# openSX70_ALADDIN_V37_20180120.net
KiCad netlist of a schematic drawn in EAGLE
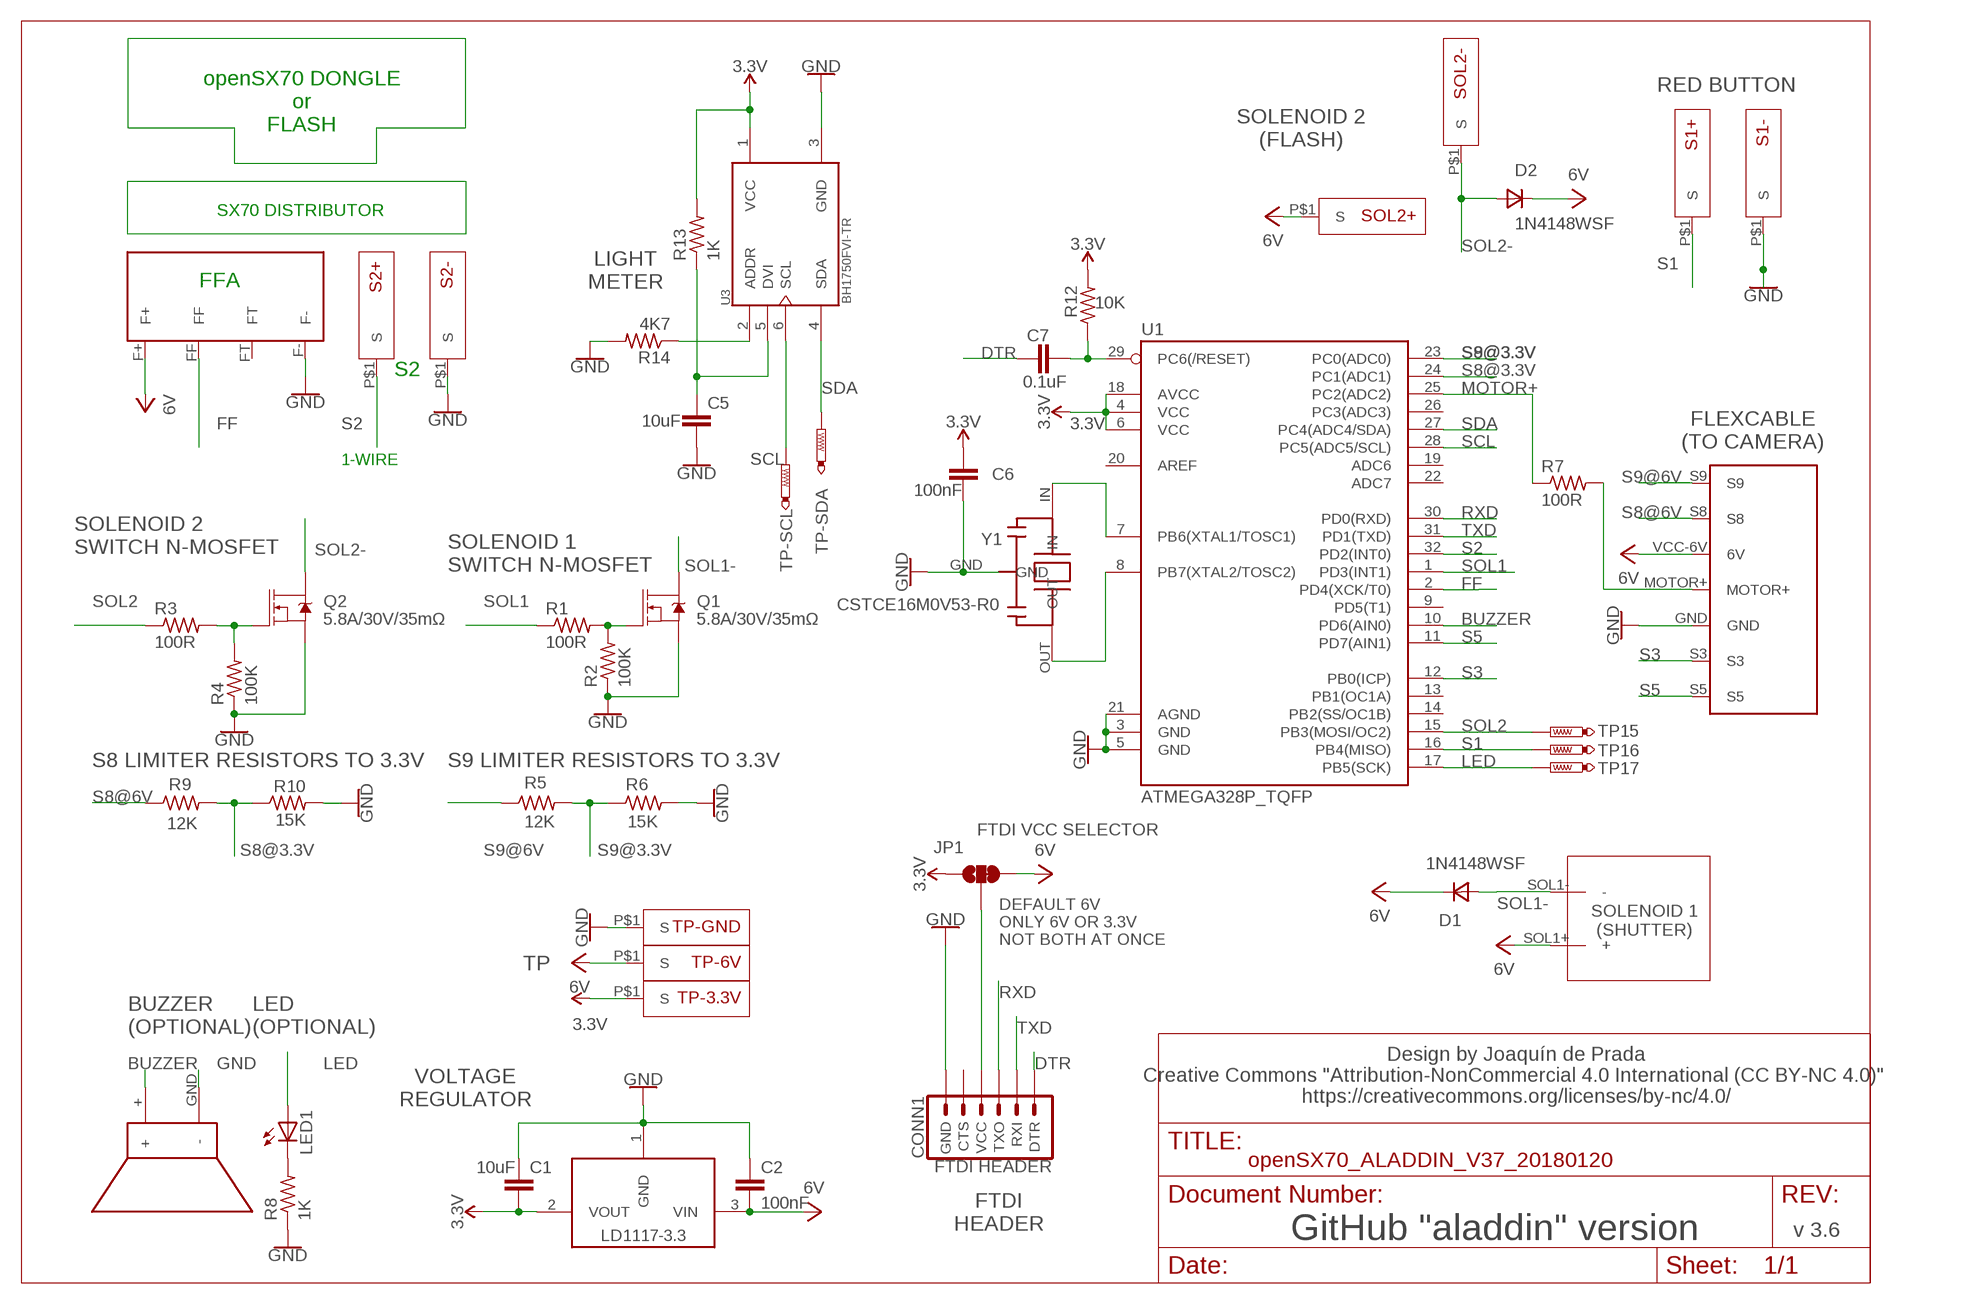
[diagram p0: schematic, sheet 1]

(export (version "E")
  (design (tool "Eeschema 10.0.6"))
  (components
    (comp (ref "BUZZ1")
      (value "CSET8-5G")
      (footprint "eagle-import:CSET8-5G_PACKAGE")
      (libsource (lib "eagle-import") (part "CSET8-5G"))
    )
    (comp (ref "C1")
      (value "10uF")
      (footprint "eagle-import:0603")
      (libsource (lib "eagle-import") (part "10UF-0603-6.3V-20%"))
    )
    (comp (ref "C2")
      (value "100nF")
      (footprint "eagle-import:C0603K")
      (libsource (lib "eagle-import") (part "C-EUC0603K"))
    )
    (comp (ref "C5")
      (value "10uF")
      (footprint "eagle-import:0603")
      (libsource (lib "eagle-import") (part "10UF-0603-6.3V-20%"))
    )
    (comp (ref "C6")
      (value "100nF")
      (footprint "eagle-import:C0603")
      (libsource (lib "eagle-import") (part "C-EUC0603"))
    )
    (comp (ref "C7")
      (value "0.1uF")
      (footprint "eagle-import:0603")
      (libsource (lib "eagle-import") (part "0.1UF-0603-25V-(+80/-20%)"))
    )
    (comp (ref "CONN1")
      (value "FTDI HEADER")
      (footprint "eagle-import:1X06")
      (libsource (lib "eagle-import") (part "6_PIN_SERIAL_TARGET"))
    )
    (comp (ref "D1")
      (value "1N4148WSF")
      (footprint "eagle-import:SOD323")
      (fields (field (name "MPN") "CDSOD323-T05C"))
      (libsource (lib "eagle-import") (part "DSOD323"))
    )
    (comp (ref "D2")
      (value "1N4148WSF")
      (footprint "eagle-import:SOD323")
      (fields (field (name "MPN") "CDSOD323-T05C"))
      (libsource (lib "eagle-import") (part "DSOD323"))
    )
    (comp (ref "JP1")
      (value "FTDI VCC SELECTOR")
      (footprint "eagle-import:SMT-JUMPER_3_1-NC_TRACE_SILK")
      (libsource (lib "eagle-import") (part "JUMPER-SMT_3_1-NC_TRACE_SILK"))
    )
    (comp (ref "LD11173.3V")
      (value "LD1117 3.3V")
      (footprint "eagle-import:SOT223")
      (fields (field (name "MF") "Advanced Monolithic Systems") (field (name "MP") "AMS1117-5.0"))
      (libsource (lib "eagle-import") (part "LD1117-3.3"))
    )
    (comp (ref "LED1")
      (value "LEDCHIPLED_0805")
      (footprint "eagle-import:CHIPLED_0805")
      (libsource (lib "eagle-import") (part "LEDCHIPLED_0805"))
    )
    (comp (ref "Q1")
      (value "5.8A/30V/35mΩ")
      (footprint "eagle-import:SOT23-3")
      (libsource (lib "eagle-import") (part "MOSFET-NCH-AO3404A"))
    )
    (comp (ref "Q2")
      (value "5.8A/30V/35mΩ")
      (footprint "eagle-import:SOT23-3")
      (libsource (lib "eagle-import") (part "MOSFET-NCH-AO3404A"))
    )
    (comp (ref "R1")
      (value "100R")
      (footprint "eagle-import:R0603")
      (libsource (lib "eagle-import") (part "R-US_R0603"))
    )
    (comp (ref "R2")
      (value "100K")
      (footprint "eagle-import:R0603")
      (libsource (lib "eagle-import") (part "R-US_R0603"))
    )
    (comp (ref "R3")
      (value "100R")
      (footprint "eagle-import:R0603")
      (libsource (lib "eagle-import") (part "R-US_R0603"))
    )
    (comp (ref "R4")
      (value "100K")
      (footprint "eagle-import:R0603")
      (libsource (lib "eagle-import") (part "R-US_R0603"))
    )
    (comp (ref "R5")
      (value "12K")
      (footprint "eagle-import:R0603")
      (libsource (lib "eagle-import") (part "R-US_R0603"))
    )
    (comp (ref "R6")
      (value "15K")
      (footprint "eagle-import:R0603")
      (libsource (lib "eagle-import") (part "R-US_R0603"))
    )
    (comp (ref "R7")
      (value "100R")
      (footprint "eagle-import:R0603")
      (libsource (lib "eagle-import") (part "R-US_R0603"))
    )
    (comp (ref "R8")
      (value "1K")
      (footprint "eagle-import:R0603")
      (libsource (lib "eagle-import") (part "R-US_R0603"))
    )
    (comp (ref "R9")
      (value "12K")
      (footprint "eagle-import:R0603")
      (libsource (lib "eagle-import") (part "R-US_R0603"))
    )
    (comp (ref "R10")
      (value "15K")
      (footprint "eagle-import:R0603")
      (libsource (lib "eagle-import") (part "R-US_R0603"))
    )
    (comp (ref "R12")
      (value "10K")
      (footprint "eagle-import:R0603")
      (libsource (lib "eagle-import") (part "R-US_R0603"))
    )
    (comp (ref "R13")
      (value "1K")
      (footprint "eagle-import:R0603")
      (libsource (lib "eagle-import") (part "R-US_R0603"))
    )
    (comp (ref "R14")
      (value "4K7")
      (footprint "eagle-import:R0603")
      (libsource (lib "eagle-import") (part "R-US_R0603"))
    )
    (comp (ref "S1+")
      (value "SX70-S-PAD-NEW")
      (footprint "eagle-import:SX70-S-PAD2")
      (libsource (lib "eagle-import") (part "SX70-S-PAD-NEW"))
    )
    (comp (ref "S1-")
      (value "SX70-S-PAD-NEW")
      (footprint "eagle-import:SX70-S-PAD2")
      (libsource (lib "eagle-import") (part "SX70-S-PAD-NEW"))
    )
    (comp (ref "S2+")
      (value "SX70-S-PAD-NEW")
      (footprint "eagle-import:SX70-S-PAD2")
      (libsource (lib "eagle-import") (part "SX70-S-PAD-NEW"))
    )
    (comp (ref "S2-")
      (value "SX70-S-PAD-NEW")
      (footprint "eagle-import:SX70-S-PAD2")
      (libsource (lib "eagle-import") (part "SX70-S-PAD-NEW"))
    )
    (comp (ref "SOL1")
      (value "SX70-SOLENOID1-2PADS")
      (footprint "eagle-import:SX70-SOLENOID1-2")
      (libsource (lib "eagle-import") (part "SX70-SOLENOID1-2PADS"))
    )
    (comp (ref "SOL2+")
      (value "SX70-S-PAD-NEW")
      (footprint "eagle-import:SX70-S-PAD2")
      (libsource (lib "eagle-import") (part "SX70-S-PAD-NEW"))
    )
    (comp (ref "SOL2-")
      (value "SX70-S-PAD-NEW")
      (footprint "eagle-import:SX70-S-PAD2")
      (libsource (lib "eagle-import") (part "SX70-S-PAD-NEW"))
    )
    (comp (ref "TP-3.3V")
      (value "SX70-S-PAD-NEW")
      (footprint "eagle-import:SX70-S-PAD2")
      (libsource (lib "eagle-import") (part "SX70-S-PAD-NEW"))
    )
    (comp (ref "TP-6V")
      (value "SX70-S-PAD-NEW")
      (footprint "eagle-import:SX70-S-PAD2")
      (libsource (lib "eagle-import") (part "SX70-S-PAD-NEW"))
    )
    (comp (ref "TP-GND")
      (value "SX70-S-PAD-NEW")
      (footprint "eagle-import:SX70-S-PAD2")
      (libsource (lib "eagle-import") (part "SX70-S-PAD-NEW"))
    )
    (comp (ref "TP-SCL")
      (value "PTR1TP08R")
      (footprint "eagle-import:TP08R")
      (libsource (lib "eagle-import") (part "PTR1TP08R"))
    )
    (comp (ref "TP-SDA")
      (value "PTR1TP08R")
      (footprint "eagle-import:TP08R")
      (libsource (lib "eagle-import") (part "PTR1TP08R"))
    )
    (comp (ref "TP15")
      (value "PTR1TP08R")
      (footprint "eagle-import:TP08R")
      (libsource (lib "eagle-import") (part "PTR1TP08R"))
    )
    (comp (ref "TP16")
      (value "PTR1TP08R")
      (footprint "eagle-import:TP08R")
      (libsource (lib "eagle-import") (part "PTR1TP08R"))
    )
    (comp (ref "TP17")
      (value "PTR1TP08R")
      (footprint "eagle-import:TP08R")
      (libsource (lib "eagle-import") (part "PTR1TP08R"))
    )
    (comp (ref "U$1")
      (value "SX70-7-PAD")
      (footprint "eagle-import:SX70-7-PAD")
      (libsource (lib "eagle-import") (part "SX70-7-PAD"))
    )
    (comp (ref "U$2")
      (value "FFA")
      (footprint "eagle-import:FFA-PAD-PACKAGE")
      (libsource (lib "eagle-import") (part "SX70-FFA-PAD"))
    )
    (comp (ref "U1")
      (value "ATMEGA328P_TQFP")
      (footprint "eagle-import:TQFP32-08")
      (libsource (lib "eagle-import") (part "ATMEGA328P_TQFP"))
    )
    (comp (ref "U3")
      (value "BH1750FVI-TR")
      (footprint "eagle-import:SOTFL50P300X75-6N")
      (fields (field (name "MF") "Rohm"))
      (libsource (lib "eagle-import") (part "BH1750FVI-TR"))
    )
    (comp (ref "Y1")
      (value "CSTCE16M0V53-R0")
      (footprint "eagle-import:CFP95P160X100-3N")
      (fields (field (name "MF") "Murata"))
      (libsource (lib "eagle-import") (part "CSTCE16M0V53-R0"))
    )
  )
  (nets
    (net (code "1") (name "/BUZZER") (class "Default")
      (node (ref "BUZZ1") (pin "+") (pinfunction "+_+") (pintype "bidirectional"))
      (node (ref "U1") (pin "10") (pinfunction "PD6(AIN0)_10") (pintype "bidirectional"))
    )
    (net (code "2") (name "/DTR") (class "Default")
      (node (ref "C7") (pin "1") (pinfunction "1_1") (pintype "passive"))
      (node (ref "CONN1") (pin "1") (pinfunction "DTR_1") (pintype "passive"))
    )
    (net (code "3") (name "/FF") (class "Default")
      (node (ref "U$2") (pin "FF") (pinfunction "FF_FF") (pintype "bidirectional"))
      (node (ref "U1") (pin "2") (pinfunction "PD4(XCK/T0)_2") (pintype "bidirectional"))
    )
    (net (code "4") (name "/LED") (class "Default")
      (node (ref "LED1") (pin "A") (pinfunction "A_A") (pintype "passive"))
      (node (ref "TP17") (pin "TP") (pinfunction "TP_TP") (pintype "input"))
      (node (ref "U1") (pin "17") (pinfunction "PB5(SCK)_17") (pintype "bidirectional"))
    )
    (net (code "5") (name "/MOTOR+") (class "Default")
      (node (ref "R7") (pin "1") (pinfunction "1_1") (pintype "passive"))
      (node (ref "U1") (pin "25") (pinfunction "PC2(ADC2)_25") (pintype "bidirectional"))
    )
    (net (code "6") (name "/RXD") (class "Default")
      (node (ref "CONN1") (pin "3") (pinfunction "TXO_3") (pintype "passive"))
      (node (ref "U1") (pin "30") (pinfunction "PD0(RXD)_30") (pintype "bidirectional"))
    )
    (net (code "7") (name "/S1") (class "Default")
      (node (ref "S1+") (pin "P$1") (pinfunction "S_P$1") (pintype "bidirectional"))
      (node (ref "TP16") (pin "TP") (pinfunction "TP_TP") (pintype "input"))
      (node (ref "U1") (pin "16") (pinfunction "PB4(MISO)_16") (pintype "bidirectional"))
    )
    (net (code "8") (name "/S2") (class "Default")
      (node (ref "S2+") (pin "P$1") (pinfunction "S_P$1") (pintype "bidirectional"))
      (node (ref "U1") (pin "32") (pinfunction "PD2(INT0)_32") (pintype "bidirectional"))
    )
    (net (code "9") (name "/S3") (class "Default")
      (node (ref "U$1") (pin "S3") (pinfunction "S3_S3") (pintype "bidirectional"))
      (node (ref "U1") (pin "12") (pinfunction "PB0(ICP)_12") (pintype "bidirectional"))
    )
    (net (code "10") (name "/S5") (class "Default")
      (node (ref "U$1") (pin "S5") (pinfunction "S5_S5") (pintype "bidirectional"))
      (node (ref "U1") (pin "11") (pinfunction "PD7(AIN1)_11") (pintype "bidirectional"))
    )
    (net (code "11") (name "/S8@3.3V") (class "Default")
      (node (ref "R10") (pin "1") (pinfunction "1_1") (pintype "passive"))
      (node (ref "R9") (pin "2") (pinfunction "2_2") (pintype "passive"))
      (node (ref "U1") (pin "24") (pinfunction "PC1(ADC1)_24") (pintype "bidirectional"))
    )
    (net (code "12") (name "/S8@6V") (class "Default")
      (node (ref "R9") (pin "1") (pinfunction "1_1") (pintype "passive"))
      (node (ref "U$1") (pin "S8") (pinfunction "S8_S8") (pintype "bidirectional"))
    )
    (net (code "13") (name "/S9@3.3V") (class "Default")
      (node (ref "R5") (pin "2") (pinfunction "2_2") (pintype "passive"))
      (node (ref "R6") (pin "1") (pinfunction "1_1") (pintype "passive"))
      (node (ref "U1") (pin "23") (pinfunction "PC0(ADC0)_23") (pintype "bidirectional"))
    )
    (net (code "14") (name "/S9@6V") (class "Default")
      (node (ref "R5") (pin "1") (pinfunction "1_1") (pintype "passive"))
      (node (ref "U$1") (pin "S9") (pinfunction "S9_S9") (pintype "bidirectional"))
    )
    (net (code "15") (name "/SCL") (class "Default")
      (node (ref "TP-SCL") (pin "TP") (pinfunction "TP_TP") (pintype "input"))
      (node (ref "U1") (pin "28") (pinfunction "PC5(ADC5/SCL)_28") (pintype "bidirectional"))
      (node (ref "U3") (pin "6") (pinfunction "SCL_6") (pintype "input"))
    )
    (net (code "16") (name "/SDA") (class "Default")
      (node (ref "TP-SDA") (pin "TP") (pinfunction "TP_TP") (pintype "input"))
      (node (ref "U1") (pin "27") (pinfunction "PC4(ADC4/SDA)_27") (pintype "bidirectional"))
      (node (ref "U3") (pin "4") (pinfunction "SDA_4") (pintype "bidirectional"))
    )
    (net (code "17") (name "/SOL1") (class "Default")
      (node (ref "R1") (pin "1") (pinfunction "1_1") (pintype "passive"))
      (node (ref "U1") (pin "1") (pinfunction "PD3(INT1)_1") (pintype "bidirectional"))
    )
    (net (code "18") (name "/SOL1-") (class "Default")
      (node (ref "D1") (pin "2") (pinfunction "A_2") (pintype "passive"))
      (node (ref "Q1") (pin "3") (pinfunction "D_3") (pintype "bidirectional"))
      (node (ref "SOL1") (pin "SOL1-") (pinfunction "-_SOL1-") (pintype "bidirectional"))
    )
    (net (code "19") (name "/SOL2") (class "Default")
      (node (ref "R3") (pin "1") (pinfunction "1_1") (pintype "passive"))
      (node (ref "TP15") (pin "TP") (pinfunction "TP_TP") (pintype "input"))
      (node (ref "U1") (pin "15") (pinfunction "PB3(MOSI/OC2)_15") (pintype "bidirectional"))
    )
    (net (code "20") (name "/SOL2-") (class "Default")
      (node (ref "D2") (pin "2") (pinfunction "A_2") (pintype "passive"))
      (node (ref "Q2") (pin "3") (pinfunction "D_3") (pintype "bidirectional"))
      (node (ref "SOL2-") (pin "P$1") (pinfunction "S_P$1") (pintype "bidirectional"))
    )
    (net (code "21") (name "/TXD") (class "Default")
      (node (ref "CONN1") (pin "2") (pinfunction "RXI_2") (pintype "passive"))
      (node (ref "U1") (pin "31") (pinfunction "PD1(TXD)_31") (pintype "bidirectional"))
    )
    (net (code "22") (name "3.3V") (class "Default")
      (node (ref "C1") (pin "2") (pinfunction "2_2") (pintype "passive"))
      (node (ref "C6") (pin "1") (pinfunction "1_1") (pintype "passive"))
      (node (ref "JP1") (pin "1") (pinfunction "1_1") (pintype "passive"))
      (node (ref "LD11173.3V") (pin "2") (pinfunction "VOUT_2") (pintype "bidirectional"))
      (node (ref "R12") (pin "2") (pinfunction "2_2") (pintype "passive"))
      (node (ref "R13") (pin "2") (pinfunction "2_2") (pintype "passive"))
      (node (ref "TP-3.3V") (pin "P$1") (pinfunction "S_P$1") (pintype "bidirectional"))
      (node (ref "U1") (pin "18") (pinfunction "AVCC_18") (pintype "bidirectional"))
      (node (ref "U1") (pin "4") (pinfunction "VCC_4") (pintype "bidirectional"))
      (node (ref "U1") (pin "6") (pinfunction "VCC_6") (pintype "bidirectional"))
      (node (ref "U3") (pin "1") (pinfunction "VCC_1") (pintype "power_in"))
    )
    (net (code "23") (name "6V") (class "Default")
      (node (ref "C2") (pin "2") (pinfunction "2_2") (pintype "passive"))
      (node (ref "D1") (pin "1") (pinfunction "C_1") (pintype "passive"))
      (node (ref "D2") (pin "1") (pinfunction "C_1") (pintype "passive"))
      (node (ref "JP1") (pin "3") (pinfunction "3_3") (pintype "passive"))
      (node (ref "LD11173.3V") (pin "3") (pinfunction "VIN_3") (pintype "bidirectional"))
      (node (ref "SOL1") (pin "SOL1+") (pinfunction "+_SOL1+") (pintype "bidirectional"))
      (node (ref "SOL2+") (pin "P$1") (pinfunction "S_P$1") (pintype "bidirectional"))
      (node (ref "TP-6V") (pin "P$1") (pinfunction "S_P$1") (pintype "bidirectional"))
      (node (ref "U$1") (pin "VCC-6V") (pinfunction "6V_VCC-6V") (pintype "bidirectional"))
      (node (ref "U$2") (pin "F+") (pinfunction "F+_F+") (pintype "bidirectional"))
    )
    (net (code "24") (name "GND") (class "Default")
      (node (ref "BUZZ1") (pin "GND") (pinfunction "-_GND") (pintype "bidirectional"))
      (node (ref "C1") (pin "1") (pinfunction "1_1") (pintype "passive"))
      (node (ref "C2") (pin "1") (pinfunction "1_1") (pintype "passive"))
      (node (ref "C5") (pin "2") (pinfunction "2_2") (pintype "passive"))
      (node (ref "C6") (pin "2") (pinfunction "2_2") (pintype "passive"))
      (node (ref "CONN1") (pin "6") (pinfunction "GND_6") (pintype "passive"))
      (node (ref "LD11173.3V") (pin "1") (pinfunction "GND_1") (pintype "bidirectional"))
      (node (ref "Q1") (pin "2") (pinfunction "S_2") (pintype "bidirectional"))
      (node (ref "Q2") (pin "2") (pinfunction "S_2") (pintype "bidirectional"))
      (node (ref "R10") (pin "2") (pinfunction "2_2") (pintype "passive"))
      (node (ref "R14") (pin "2") (pinfunction "2_2") (pintype "passive"))
      (node (ref "R2") (pin "1") (pinfunction "1_1") (pintype "passive"))
      (node (ref "R4") (pin "1") (pinfunction "1_1") (pintype "passive"))
      (node (ref "R6") (pin "2") (pinfunction "2_2") (pintype "passive"))
      (node (ref "R8") (pin "1") (pinfunction "1_1") (pintype "passive"))
      (node (ref "S1-") (pin "P$1") (pinfunction "S_P$1") (pintype "bidirectional"))
      (node (ref "S2-") (pin "P$1") (pinfunction "S_P$1") (pintype "bidirectional"))
      (node (ref "TP-GND") (pin "P$1") (pinfunction "S_P$1") (pintype "bidirectional"))
      (node (ref "U$1") (pin "GND") (pinfunction "GND_GND") (pintype "bidirectional"))
      (node (ref "U$2") (pin "F-") (pinfunction "F-_F-") (pintype "bidirectional"))
      (node (ref "U1") (pin "21") (pinfunction "AGND_21") (pintype "bidirectional"))
      (node (ref "U1") (pin "3") (pinfunction "GND_3") (pintype "bidirectional"))
      (node (ref "U1") (pin "5") (pinfunction "GND_5") (pintype "bidirectional"))
      (node (ref "U3") (pin "3") (pinfunction "GND_3") (pintype "power_in"))
      (node (ref "Y1") (pin "GND") (pinfunction "GND_GND") (pintype "passive"))
    )
    (net (code "25") (name "Net-(CONN1-VCC)") (class "Default")
      (node (ref "CONN1") (pin "4") (pinfunction "VCC_4") (pintype "passive"))
      (node (ref "JP1") (pin "2") (pinfunction "2_2") (pintype "passive"))
    )
    (net (code "26") (name "Net-(LED1-PadC)") (class "Default")
      (node (ref "LED1") (pin "C") (pinfunction "C_C") (pintype "passive"))
      (node (ref "R8") (pin "2") (pinfunction "2_2") (pintype "passive"))
    )
    (net (code "27") (name "Net-(Q1-G)") (class "Default")
      (node (ref "Q1") (pin "1") (pinfunction "G_1") (pintype "bidirectional"))
      (node (ref "R1") (pin "2") (pinfunction "2_2") (pintype "passive"))
      (node (ref "R2") (pin "2") (pinfunction "2_2") (pintype "passive"))
    )
    (net (code "28") (name "Net-(Q2-G)") (class "Default")
      (node (ref "Q2") (pin "1") (pinfunction "G_1") (pintype "bidirectional"))
      (node (ref "R3") (pin "2") (pinfunction "2_2") (pintype "passive"))
      (node (ref "R4") (pin "2") (pinfunction "2_2") (pintype "passive"))
    )
    (net (code "29") (name "Net-(R7-Pad2)") (class "Default")
      (node (ref "R7") (pin "2") (pinfunction "2_2") (pintype "passive"))
      (node (ref "U$1") (pin "MOTOR+") (pinfunction "MOTOR+_MOTOR+") (pintype "bidirectional"))
    )
    (net (code "30") (name "Net-(U1-PB6(XTAL1{slash}TOSC1))") (class "Default")
      (node (ref "U1") (pin "7") (pinfunction "PB6(XTAL1/TOSC1)_7") (pintype "bidirectional"))
      (node (ref "Y1") (pin "IN") (pinfunction "IN_IN") (pintype "input"))
    )
    (net (code "31") (name "Net-(U1-PB7(XTAL2{slash}TOSC2))") (class "Default")
      (node (ref "U1") (pin "8") (pinfunction "PB7(XTAL2/TOSC2)_8") (pintype "bidirectional"))
      (node (ref "Y1") (pin "OUT") (pinfunction "OUT_OUT") (pintype "output"))
    )
    (net (code "32") (name "Net-(U1-PC6({slash}RESET))") (class "Default")
      (node (ref "C7") (pin "2") (pinfunction "2_2") (pintype "passive"))
      (node (ref "R12") (pin "1") (pinfunction "1_1") (pintype "passive"))
      (node (ref "U1") (pin "29") (pinfunction "PC6(/RESET)_29") (pintype "bidirectional"))
    )
    (net (code "33") (name "Net-(U3-ADDR)") (class "Default")
      (node (ref "R14") (pin "1") (pinfunction "1_1") (pintype "passive"))
      (node (ref "U3") (pin "2") (pinfunction "ADDR_2") (pintype "input"))
    )
    (net (code "34") (name "Net-(U3-DVI)") (class "Default")
      (node (ref "C5") (pin "1") (pinfunction "1_1") (pintype "passive"))
      (node (ref "R13") (pin "1") (pinfunction "1_1") (pintype "passive"))
      (node (ref "U3") (pin "5") (pinfunction "DVI_5") (pintype "input"))
    )
    (net (code "35") (name "unconnected-(CONN1-CTS-Pad5)") (class "Default")
      (node (ref "CONN1") (pin "5") (pinfunction "CTS_5") (pintype "passive"))
    )
    (net (code "36") (name "unconnected-(U$2-PadFT)") (class "Default")
      (node (ref "U$2") (pin "FT") (pinfunction "FT_FT") (pintype "bidirectional"))
    )
    (net (code "37") (name "unconnected-(U1-ADC6-Pad19)") (class "Default")
      (node (ref "U1") (pin "19") (pinfunction "ADC6_19") (pintype "bidirectional"))
    )
    (net (code "38") (name "unconnected-(U1-ADC7-Pad22)") (class "Default")
      (node (ref "U1") (pin "22") (pinfunction "ADC7_22") (pintype "bidirectional"))
    )
    (net (code "39") (name "unconnected-(U1-AREF-Pad20)") (class "Default")
      (node (ref "U1") (pin "20") (pinfunction "AREF_20") (pintype "bidirectional"))
    )
    (net (code "40") (name "unconnected-(U1-PB1(OC1A)-Pad13)") (class "Default")
      (node (ref "U1") (pin "13") (pinfunction "PB1(OC1A)_13") (pintype "bidirectional"))
    )
    (net (code "41") (name "unconnected-(U1-PB2(SS{slash}OC1B)-Pad14)") (class "Default")
      (node (ref "U1") (pin "14") (pinfunction "PB2(SS/OC1B)_14") (pintype "bidirectional"))
    )
    (net (code "42") (name "unconnected-(U1-PC3(ADC3)-Pad26)") (class "Default")
      (node (ref "U1") (pin "26") (pinfunction "PC3(ADC3)_26") (pintype "bidirectional"))
    )
    (net (code "43") (name "unconnected-(U1-PD5(T1)-Pad9)") (class "Default")
      (node (ref "U1") (pin "9") (pinfunction "PD5(T1)_9") (pintype "bidirectional"))
    )
  )
)
